# MCU.net
KiCad netlist of a schematic drawn in Altium Designer
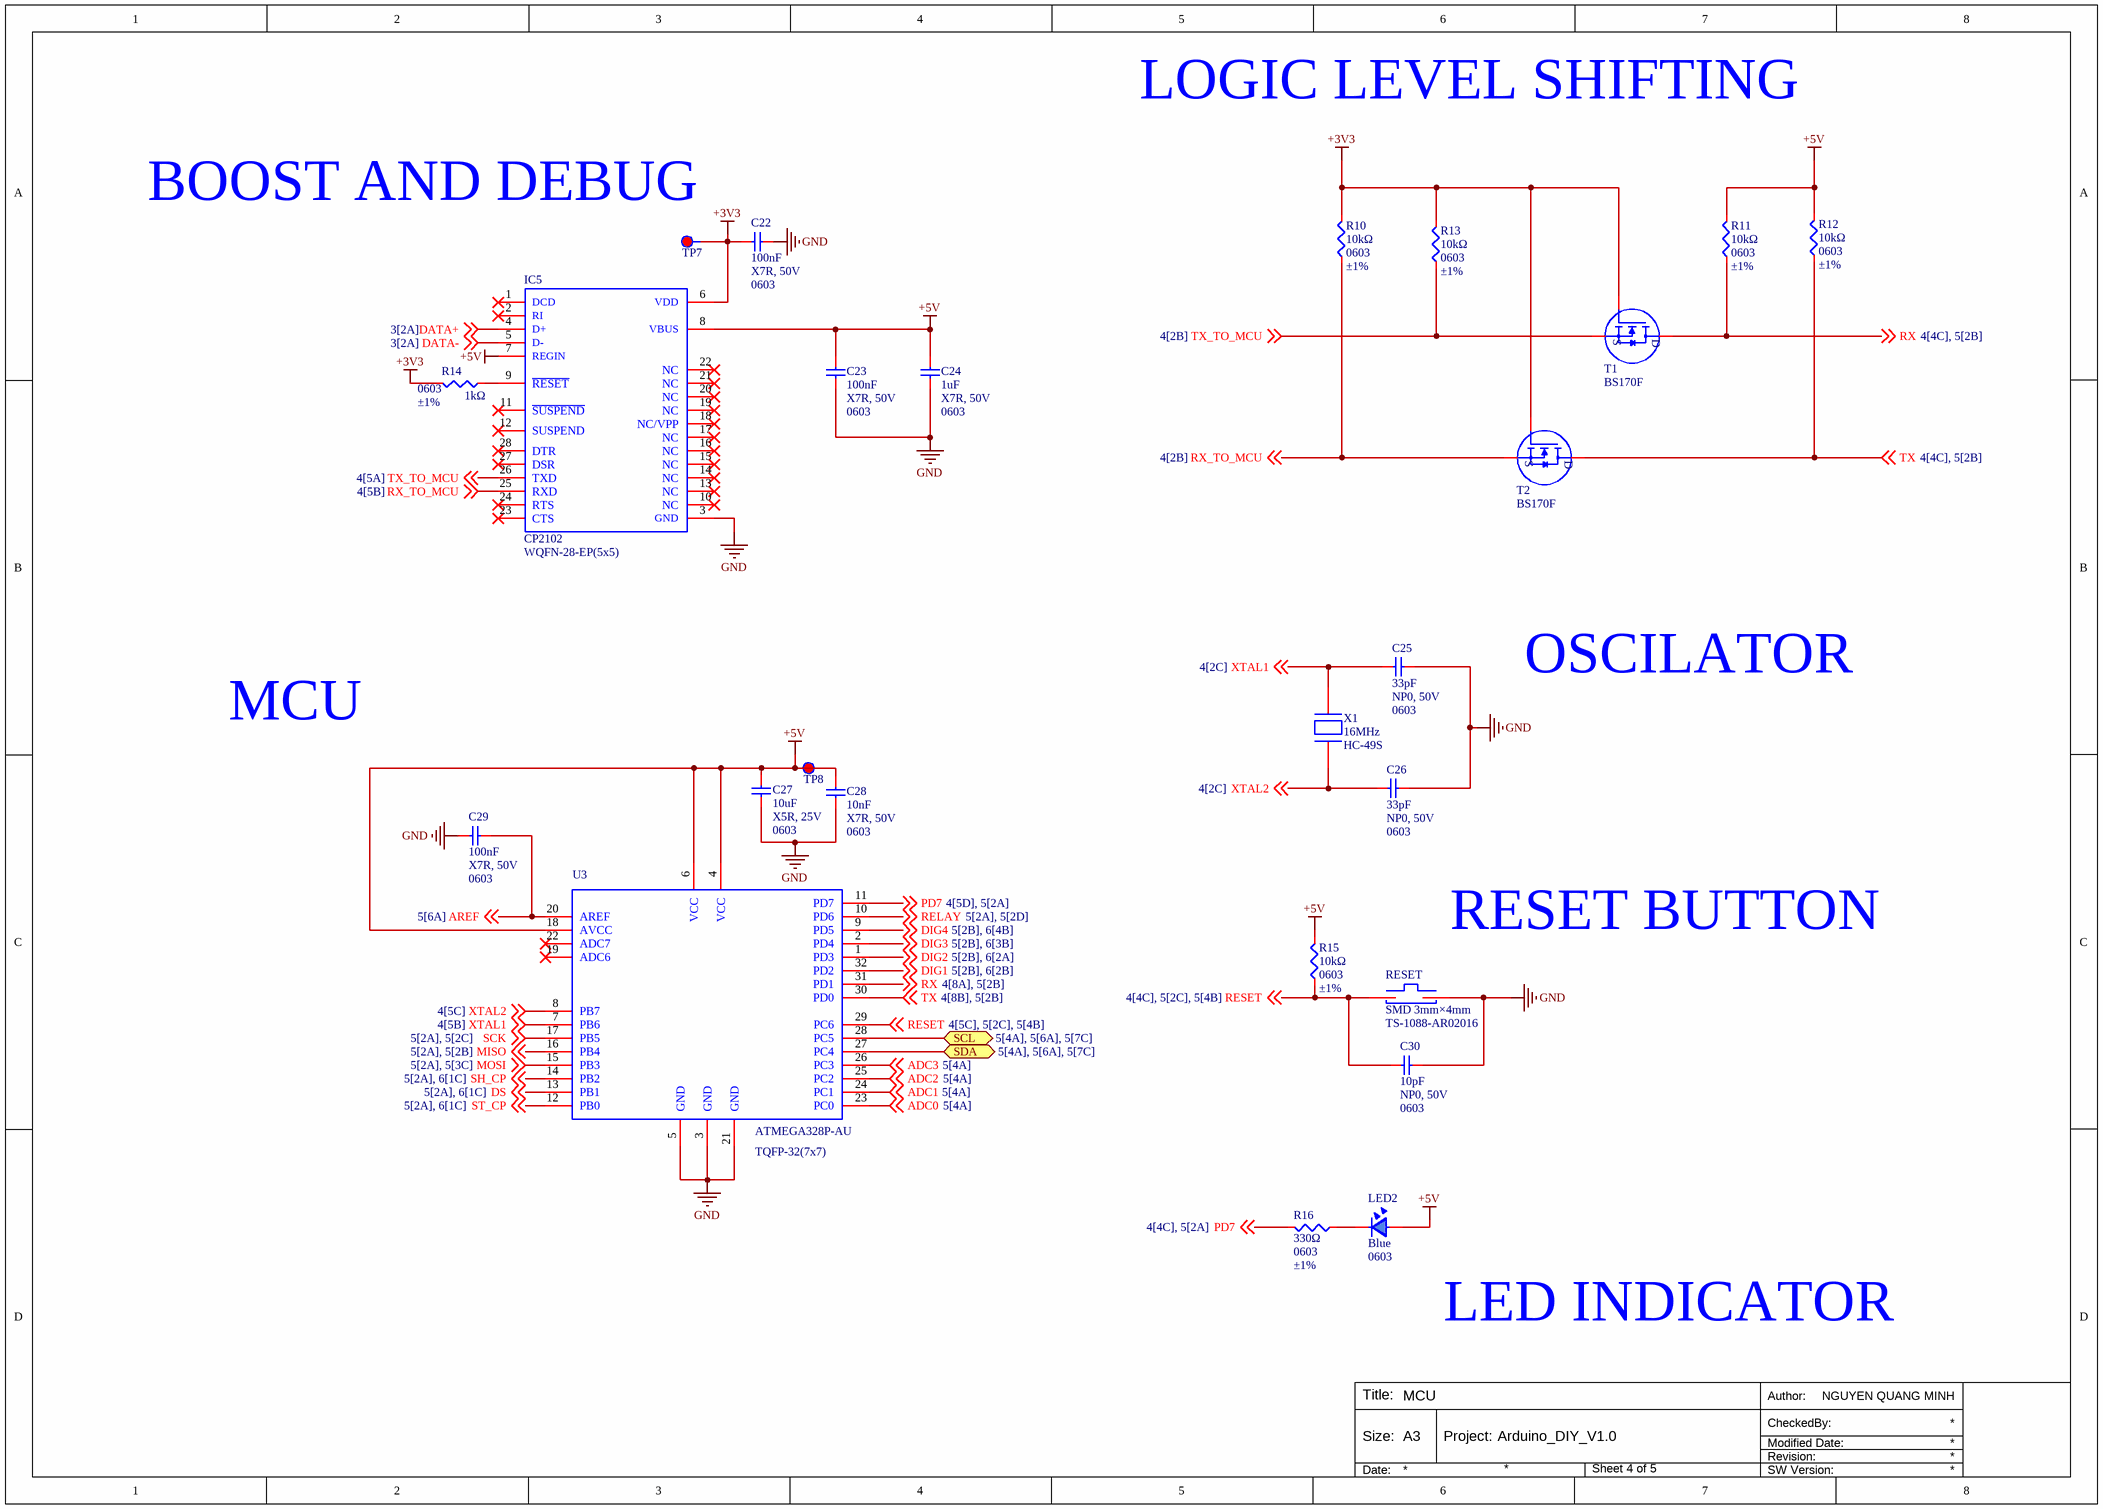
[diagram p0: MCU.SchDoc]

(export (version "E")
  (design (tool "Eeschema 10.0.6"))
  (components
    (comp (ref "C22")
      (value "100nF")
      (footprint "C0603")
      (description "50V 100nF X7R ±10% 0603 Multilayer Ceramic Capacitors MLCC - SMD/SMT ROHS")
      (fields
        (field (name "MANUFACTURER") "YAGEO")
        (field (name "MFR. PART") "CC0603KRX7R9BB104")
        (field (name "TEMPERATURE COEFFICIENT") "X7R, 50V")
        (field (name "PACKAGE") "0603")
      )
      (libsource (lib "Capacitor") (part "C0603_MLCC_100nF_X7R_50V"))
    )
    (comp (ref "C23")
      (value "100nF")
      (footprint "C0603")
      (description "50V 100nF X7R ±10% 0603 Multilayer Ceramic Capacitors MLCC - SMD/SMT ROHS")
      (fields
        (field (name "MANUFACTURER") "YAGEO")
        (field (name "MFR. PART") "CC0603KRX7R9BB104")
        (field (name "TEMPERATURE COEFFICIENT") "X7R, 50V")
        (field (name "PACKAGE") "0603")
      )
      (libsource (lib "Capacitor") (part "C0603_MLCC_100nF_X7R_50V"))
    )
    (comp (ref "C24")
      (value "1uF")
      (footprint "C0603")
      (description "50V 1uF X7R ±10% 0603 Multilayer Ceramic Capacitors MLCC - SMD/SMT ROHS")
      (fields
        (field (name "MANUFACTURER") "YAGEO")
        (field (name "MFR. PART") "CC0603KRX7R9BB105")
        (field (name "TEMPERATURE COEFFICIENT") "X7R, 50V")
        (field (name "PACKAGE") "0603")
      )
      (libsource (lib "Capacitor") (part "C0603_MLCC_1uF_X7R_50V"))
    )
    (comp (ref "C25")
      (value "33pF")
      (footprint "C0603")
      (description "50V 33pF NP0 ±5% 0603 Multilayer Ceramic Capacitors MLCC - SMD/SMT ROHS")
      (fields
        (field (name "MANUFACTURER") "YAGEO")
        (field (name "MFR. PART") "CC0603JRNPO9BN330")
        (field (name "TEMPERATURE COEFFICIENT") "NP0, 50V")
        (field (name "PACKAGE") "0603")
      )
      (libsource (lib "Capacitor") (part "C0603_MLCC_33pF_NP0_50V"))
    )
    (comp (ref "C26")
      (value "33pF")
      (footprint "C0603")
      (description "50V 33pF NP0 ±5% 0603 Multilayer Ceramic Capacitors MLCC - SMD/SMT ROHS")
      (fields
        (field (name "MANUFACTURER") "YAGEO")
        (field (name "MFR. PART") "CC0603JRNPO9BN330")
        (field (name "TEMPERATURE COEFFICIENT") "NP0, 50V")
        (field (name "PACKAGE") "0603")
      )
      (libsource (lib "Capacitor") (part "C0603_MLCC_33pF_NP0_50V"))
    )
    (comp (ref "C27")
      (value "10uF")
      (footprint "C0603")
      (description "25V 10uF X5R ±20% 0603 Multilayer Ceramic Capacitors MLCC - SMD/SMT ROHS")
      (fields
        (field (name "MANUFACTURER") "YAGEO")
        (field (name "MFR. PART") "CC0603MRX5R8BB106")
        (field (name "TEMPERATURE COEFFICIENT") "X5R, 25V")
        (field (name "PACKAGE") "0603")
      )
      (libsource (lib "Capacitor") (part "C0603_MLCC_10uF_X5R_25V"))
    )
    (comp (ref "C28")
      (value "10nF")
      (footprint "C0603")
      (description "50V 10nF X7R ±10% 0603 Multilayer Ceramic Capacitors MLCC - SMD/SMT ROHS")
      (fields
        (field (name "MANUFACTURER") "YAGEO")
        (field (name "MFR. PART") "CC0603KRX7R9BB103")
        (field (name "TEMPERATURE COEFFICIENT") "X7R, 50V")
        (field (name "PACKAGE") "0603")
      )
      (libsource (lib "Capacitor") (part "C0603_MLCC_10nF_X7R_50V"))
    )
    (comp (ref "C29")
      (value "100nF")
      (footprint "C0603")
      (description "50V 100nF X7R ±10% 0603 Multilayer Ceramic Capacitors MLCC - SMD/SMT ROHS")
      (fields
        (field (name "MANUFACTURER") "YAGEO")
        (field (name "MFR. PART") "CC0603KRX7R9BB104")
        (field (name "TEMPERATURE COEFFICIENT") "X7R, 50V")
        (field (name "PACKAGE") "0603")
      )
      (libsource (lib "Capacitor") (part "C0603_MLCC_100nF_X7R_50V"))
    )
    (comp (ref "C30")
      (value "10pF")
      (footprint "C0603")
      (description "50V 10pF NP0 ±5% 0603 Multilayer Ceramic Capacitors MLCC - SMD/SMT ROHS")
      (fields
        (field (name "MANUFACTURER") "YAGEO")
        (field (name "MFR. PART") "CC0603JRNPO9BN100")
        (field (name "TEMPERATURE COEFFICIENT") "NP0, 50V")
        (field (name "PACKAGE") "0603")
      )
      (libsource (lib "Capacitor") (part "C0603_MLCC_10pF_NP0_50V"))
    )
    (comp (ref "IC5")
      (value "CP2102")
      (footprint "WQFN-28-EP(5x5)")
      (description "12Mbps Transceiver WQFN-28-EP(5x5) USB Converters ROHS")
      (fields
        (field (name "MANUFACTURER") "SILICON LABS")
        (field (name "MFR. PART") "CP2102-GMR")
        (field (name "PACKAGE") "WQFN-28-EP(5x5)")
      )
      (libsource (lib "IC") (part "CP2102"))
    )
    (comp (ref "LED2")
      (value "Blue")
      (footprint "LED0603_BLUE")
      (description "2mA 24mcd Water Clear -40℃~+85℃ 470nm Blue 130° 120mW 2.65V 0603 LED Indication - Discrete ROHS")
      (fields
        (field (name "MANUFACTURER") "Kingbright")
        (field (name "MFR. PART") "APT1608LVBC/D")
        (field (name "PACKAGE") "0603")
      )
      (libsource (lib "LED") (part "LED0603_Blue"))
    )
    (comp (ref "R10")
      (value "10kΩ")
      (footprint "R0603")
      (description "100mW Thick Film Resistor 75V ±100ppm/℃ ±1% 10kΩ 0603 Chip Resistor - Surface Mount ROHS")
      (fields
        (field (name "MANUFACTURER") "YAGEO")
        (field (name "MFR. PART") "RC0603FR-0710KL")
        (field (name "PACKAGE") "0603")
        (field (name "TOLERANCE") "±1%")
      )
      (libsource (lib "Resistor") (part "R0603_10kΩ_±1%"))
    )
    (comp (ref "R11")
      (value "10kΩ")
      (footprint "R0603")
      (description "100mW Thick Film Resistor 75V ±100ppm/℃ ±1% 10kΩ 0603 Chip Resistor - Surface Mount ROHS")
      (fields
        (field (name "MANUFACTURER") "YAGEO")
        (field (name "MFR. PART") "RC0603FR-0710KL")
        (field (name "PACKAGE") "0603")
        (field (name "TOLERANCE") "±1%")
      )
      (libsource (lib "Resistor") (part "R0603_10kΩ_±1%"))
    )
    (comp (ref "R12")
      (value "10kΩ")
      (footprint "R0603")
      (description "100mW Thick Film Resistor 75V ±100ppm/℃ ±1% 10kΩ 0603 Chip Resistor - Surface Mount ROHS")
      (fields
        (field (name "MANUFACTURER") "YAGEO")
        (field (name "MFR. PART") "RC0603FR-0710KL")
        (field (name "PACKAGE") "0603")
        (field (name "TOLERANCE") "±1%")
      )
      (libsource (lib "Resistor") (part "R0603_10kΩ_±1%"))
    )
    (comp (ref "R13")
      (value "10kΩ")
      (footprint "R0603")
      (description "100mW Thick Film Resistor 75V ±100ppm/℃ ±1% 10kΩ 0603 Chip Resistor - Surface Mount ROHS")
      (fields
        (field (name "MANUFACTURER") "YAGEO")
        (field (name "MFR. PART") "RC0603FR-0710KL")
        (field (name "PACKAGE") "0603")
        (field (name "TOLERANCE") "±1%")
      )
      (libsource (lib "Resistor") (part "R0603_10kΩ_±1%"))
    )
    (comp (ref "R14")
      (value "1kΩ")
      (footprint "R0603")
      (description "100mW Thick Film Resistor 75V ±100ppm/℃ ±1% 1kΩ 0603 Chip Resistor - Surface Mount ROHS")
      (fields
        (field (name "MANUFACTURER") "YAGEO")
        (field (name "MFR. PART") "RC0603FR-071KL")
        (field (name "PACKAGE") "0603")
        (field (name "TOLERANCE") "±1%")
      )
      (libsource (lib "Resistor") (part "R0603_1kΩ_±1%"))
    )
    (comp (ref "R15")
      (value "10kΩ")
      (footprint "R0603")
      (description "100mW Thick Film Resistor 75V ±100ppm/℃ ±1% 10kΩ 0603 Chip Resistor - Surface Mount ROHS")
      (fields
        (field (name "MANUFACTURER") "YAGEO")
        (field (name "MFR. PART") "RC0603FR-0710KL")
        (field (name "PACKAGE") "0603")
        (field (name "TOLERANCE") "±1%")
      )
      (libsource (lib "Resistor") (part "R0603_10kΩ_±1%"))
    )
    (comp (ref "R16")
      (value "330Ω")
      (footprint "R0603")
      (description "100mW Thick Film Resistor 75V ±100ppm/℃ ±1% 330Ω 0603 Chip Resistor - Surface Mount ROHS")
      (fields
        (field (name "MANUFACTURER") "YAGEO")
        (field (name "MFR. PART") "RC0603FR-07330RL")
        (field (name "PACKAGE") "0603")
        (field (name "TOLERANCE") "±1%")
      )
      (libsource (lib "Resistor") (part "R0603_330Ω_±1%"))
    )
    (comp (ref "RESET")
      (value "SMD 3mm×4mm")
      (footprint "ROUND_BUTTON_SMD 3*4mm")
      (fields
        (field (name "MANUFACTURER") "XUNPU")
        (field (name "LCSC PART") "C720477")
        (field (name "MFR. PART") "TS-1088-AR02016")
      )
      (libsource (lib "BUTTON and SWITCH") (part "SW_BUTTON_SMD_3mm×4mm"))
    )
    (comp (ref "T1")
      (value "BS170F")
      (footprint "SOT-23")
      (description "90V 150uA 5Ω@10V 330mW 3V@1mA 1 N-Channel SOT-23 MOSFETs ROHS")
      (fields (field (name "MANUFACTURER") "DIODES") (field (name "LCSC PART") "C151050"))
      (libsource (lib "BJT and FET") (part "BS170F"))
    )
    (comp (ref "T2")
      (value "BS170F")
      (footprint "SOT-23")
      (description "90V 150uA 5Ω@10V 330mW 3V@1mA 1 N-Channel SOT-23 MOSFETs ROHS")
      (fields (field (name "MANUFACTURER") "DIODES") (field (name "LCSC PART") "C151050"))
      (libsource (lib "BJT and FET") (part "BS170F"))
    )
    (comp (ref "TP7")
      (value "Test Point")
      (footprint "TEST_POINT")
      (libsource (lib "TEST_POINT") (part "TEST_POINT"))
    )
    (comp (ref "TP8")
      (value "Test Point")
      (footprint "TEST_POINT")
      (libsource (lib "TEST_POINT") (part "TEST_POINT"))
    )
    (comp (ref "U3")
      (value "ATMEGA328P-AU")
      (footprint "TQFP-32 (7x7)")
      (description "AVR 20MHz TQFP-32(7x7) Microcontrollers (MCU/MPU/SOC) ROHS")
      (fields
        (field (name "MANUFACTURER") "MICROCHIP")
        (field (name "LCSC PART") "C14877")
        (field (name "PACKAGE") "TQFP-32(7x7)")
      )
      (libsource (lib "MCU") (part "ATMEGA328P-AU"))
    )
    (comp (ref "X1")
      (value "16MHz")
      (footprint "HC-49S")
      (description "16MHz Through Hole Crystal Oscillator 20pF ±20ppm ±30ppm HC-49S Crystals ROHS")
      (fields
        (field (name "MANUFACTURER") "YXC Crystal Oscillators")
        (field (name "MFR. PART") "X49SD16MSD2SC")
        (field (name "PACKAGE") "HC-49S")
      )
      (libsource (lib "CRYSTAL") (part "Crystal_16Mhz_HC49S"))
    )
  )
  (nets
    (net (code "1") (name "+3V3") (class "Default")
      (node (ref "C22") (pin "2") (pinfunction "2_2") (pintype "passive"))
      (node (ref "IC5") (pin "6") (pinfunction "VDD_6") (pintype "passive"))
      (node (ref "R10") (pin "2") (pinfunction "2_2") (pintype "passive"))
      (node (ref "R13") (pin "2") (pinfunction "2_2") (pintype "passive"))
      (node (ref "R14") (pin "2") (pinfunction "2_2") (pintype "passive"))
      (node (ref "T1") (pin "1") (pinfunction "G_1") (pintype "passive"))
      (node (ref "T2") (pin "1") (pinfunction "G_1") (pintype "passive"))
      (node (ref "TP7") (pin "1") (pinfunction "1_1") (pintype "passive"))
    )
    (net (code "2") (name "+5V") (class "Default")
      (node (ref "C23") (pin "2") (pinfunction "2_2") (pintype "passive"))
      (node (ref "C24") (pin "2") (pinfunction "2_2") (pintype "passive"))
      (node (ref "C27") (pin "2") (pinfunction "2_2") (pintype "passive"))
      (node (ref "C28") (pin "2") (pinfunction "2_2") (pintype "passive"))
      (node (ref "IC5") (pin "7") (pinfunction "REGIN_7") (pintype "passive"))
      (node (ref "IC5") (pin "8") (pinfunction "VBUS_8") (pintype "passive"))
      (node (ref "LED2") (pin "1") (pinfunction "1_1") (pintype "passive"))
      (node (ref "R11") (pin "2") (pinfunction "2_2") (pintype "passive"))
      (node (ref "R12") (pin "2") (pinfunction "2_2") (pintype "passive"))
      (node (ref "R15") (pin "2") (pinfunction "2_2") (pintype "passive"))
      (node (ref "TP8") (pin "1") (pinfunction "1_1") (pintype "passive"))
      (node (ref "U3") (pin "18") (pinfunction "AVCC_18") (pintype "passive"))
      (node (ref "U3") (pin "4") (pinfunction "VCC_4") (pintype "passive"))
      (node (ref "U3") (pin "6") (pinfunction "VCC_6") (pintype "passive"))
    )
    (net (code "3") (name "/SCL") (class "Default")
      (node (ref "U3") (pin "28") (pinfunction "PC5_28") (pintype "passive"))
    )
    (net (code "4") (name "/SDA") (class "Default")
      (node (ref "U3") (pin "27") (pinfunction "PC4_27") (pintype "passive"))
    )
    (net (code "5") (name "ADC0") (class "Default")
      (node (ref "U3") (pin "23") (pinfunction "PC0_23") (pintype "passive"))
    )
    (net (code "6") (name "ADC1") (class "Default")
      (node (ref "U3") (pin "24") (pinfunction "PC1_24") (pintype "passive"))
    )
    (net (code "7") (name "ADC2") (class "Default")
      (node (ref "U3") (pin "25") (pinfunction "PC2_25") (pintype "passive"))
    )
    (net (code "8") (name "ADC3") (class "Default")
      (node (ref "U3") (pin "26") (pinfunction "PC3_26") (pintype "passive"))
    )
    (net (code "9") (name "AREF") (class "Default")
      (node (ref "C29") (pin "2") (pinfunction "2_2") (pintype "passive"))
      (node (ref "U3") (pin "20") (pinfunction "AREF_20") (pintype "passive"))
    )
    (net (code "10") (name "DATA+") (class "Default")
      (node (ref "IC5") (pin "4") (pinfunction "D+_4") (pintype "passive"))
    )
    (net (code "11") (name "DATA-") (class "Default")
      (node (ref "IC5") (pin "5") (pinfunction "D-_5") (pintype "passive"))
    )
    (net (code "12") (name "DIG1") (class "Default")
      (node (ref "U3") (pin "32") (pinfunction "PD2_32") (pintype "passive"))
    )
    (net (code "13") (name "DIG2") (class "Default")
      (node (ref "U3") (pin "1") (pinfunction "PD3_1") (pintype "passive"))
    )
    (net (code "14") (name "DIG3") (class "Default")
      (node (ref "U3") (pin "2") (pinfunction "PD4_2") (pintype "passive"))
    )
    (net (code "15") (name "DIG4") (class "Default")
      (node (ref "U3") (pin "9") (pinfunction "PD5_9") (pintype "passive"))
    )
    (net (code "16") (name "DS") (class "Default")
      (node (ref "U3") (pin "13") (pinfunction "PB1_13") (pintype "passive"))
    )
    (net (code "17") (name "GND") (class "Default")
      (node (ref "C22") (pin "1") (pinfunction "1_1") (pintype "passive"))
      (node (ref "C23") (pin "1") (pinfunction "1_1") (pintype "passive"))
      (node (ref "C24") (pin "1") (pinfunction "1_1") (pintype "passive"))
      (node (ref "C25") (pin "2") (pinfunction "2_2") (pintype "passive"))
      (node (ref "C26") (pin "2") (pinfunction "2_2") (pintype "passive"))
      (node (ref "C27") (pin "1") (pinfunction "1_1") (pintype "passive"))
      (node (ref "C28") (pin "1") (pinfunction "1_1") (pintype "passive"))
      (node (ref "C29") (pin "1") (pinfunction "1_1") (pintype "passive"))
      (node (ref "C30") (pin "2") (pinfunction "2_2") (pintype "passive"))
      (node (ref "IC5") (pin "3") (pinfunction "GND_3") (pintype "passive"))
      (node (ref "RESET") (pin "2") (pinfunction "2_2") (pintype "passive"))
      (node (ref "U3") (pin "21") (pinfunction "GND_21") (pintype "passive"))
      (node (ref "U3") (pin "3") (pinfunction "GND_3") (pintype "passive"))
      (node (ref "U3") (pin "5") (pinfunction "GND_5") (pintype "passive"))
    )
    (net (code "18") (name "MISO") (class "Default")
      (node (ref "U3") (pin "16") (pinfunction "PB4_16") (pintype "passive"))
    )
    (net (code "19") (name "MOSI") (class "Default")
      (node (ref "U3") (pin "15") (pinfunction "PB3_15") (pintype "passive"))
    )
    (net (code "20") (name "Net-(IC5-~{RESET})") (class "Default")
      (node (ref "IC5") (pin "9") (pinfunction "~{RESET}_9") (pintype "passive"))
      (node (ref "R14") (pin "1") (pinfunction "1_1") (pintype "passive"))
    )
    (net (code "21") (name "Net-(LED2-Pad2)") (class "Default")
      (node (ref "LED2") (pin "2") (pinfunction "2_2") (pintype "passive"))
      (node (ref "R16") (pin "2") (pinfunction "2_2") (pintype "passive"))
    )
    (net (code "22") (name "PD7") (class "Default")
      (node (ref "R16") (pin "1") (pinfunction "1_1") (pintype "passive"))
      (node (ref "U3") (pin "11") (pinfunction "PD7_11") (pintype "passive"))
    )
    (net (code "23") (name "RELAY") (class "Default")
      (node (ref "U3") (pin "10") (pinfunction "PD6_10") (pintype "passive"))
    )
    (net (code "24") (name "RESET") (class "Default")
      (node (ref "C30") (pin "1") (pinfunction "1_1") (pintype "passive"))
      (node (ref "R15") (pin "1") (pinfunction "1_1") (pintype "passive"))
      (node (ref "RESET") (pin "1") (pinfunction "1_1") (pintype "passive"))
      (node (ref "U3") (pin "29") (pinfunction "PC6_29") (pintype "passive"))
    )
    (net (code "25") (name "RX") (class "Default")
      (node (ref "R11") (pin "1") (pinfunction "1_1") (pintype "passive"))
      (node (ref "T1") (pin "3") (pinfunction "D_3") (pintype "passive"))
      (node (ref "U3") (pin "31") (pinfunction "PD1_31") (pintype "passive"))
    )
    (net (code "26") (name "RX_TO_MCU") (class "Default")
      (node (ref "IC5") (pin "25") (pinfunction "RXD_25") (pintype "passive"))
      (node (ref "R10") (pin "1") (pinfunction "1_1") (pintype "passive"))
      (node (ref "T2") (pin "2") (pinfunction "S_2") (pintype "passive"))
    )
    (net (code "27") (name "SCK") (class "Default")
      (node (ref "U3") (pin "17") (pinfunction "PB5_17") (pintype "passive"))
    )
    (net (code "28") (name "SH_CP") (class "Default")
      (node (ref "U3") (pin "14") (pinfunction "PB2_14") (pintype "passive"))
    )
    (net (code "29") (name "ST_CP") (class "Default")
      (node (ref "U3") (pin "12") (pinfunction "PB0_12") (pintype "passive"))
    )
    (net (code "30") (name "TX") (class "Default")
      (node (ref "R12") (pin "1") (pinfunction "1_1") (pintype "passive"))
      (node (ref "T2") (pin "3") (pinfunction "D_3") (pintype "passive"))
      (node (ref "U3") (pin "30") (pinfunction "PD0_30") (pintype "passive"))
    )
    (net (code "31") (name "TX_TO_MCU") (class "Default")
      (node (ref "IC5") (pin "26") (pinfunction "TXD_26") (pintype "passive"))
      (node (ref "R13") (pin "1") (pinfunction "1_1") (pintype "passive"))
      (node (ref "T1") (pin "2") (pinfunction "S_2") (pintype "passive"))
    )
    (net (code "32") (name "XTAL1") (class "Default")
      (node (ref "C25") (pin "1") (pinfunction "1_1") (pintype "passive"))
      (node (ref "U3") (pin "7") (pinfunction "PB6_7") (pintype "passive"))
      (node (ref "X1") (pin "2") (pinfunction "2_2") (pintype "passive"))
    )
    (net (code "33") (name "XTAL2") (class "Default")
      (node (ref "C26") (pin "1") (pinfunction "1_1") (pintype "passive"))
      (node (ref "U3") (pin "8") (pinfunction "PB7_8") (pintype "passive"))
      (node (ref "X1") (pin "1") (pinfunction "1_1") (pintype "passive"))
    )
    (net (code "34") (name "unconnected-(IC5-CTS-Pad23)") (class "Default")
      (node (ref "IC5") (pin "23") (pinfunction "CTS_23") (pintype "passive+no_connect"))
    )
    (net (code "35") (name "unconnected-(IC5-DCD-Pad1)") (class "Default")
      (node (ref "IC5") (pin "1") (pinfunction "DCD_1") (pintype "passive+no_connect"))
    )
    (net (code "36") (name "unconnected-(IC5-DSR-Pad27)") (class "Default")
      (node (ref "IC5") (pin "27") (pinfunction "DSR_27") (pintype "passive+no_connect"))
    )
    (net (code "37") (name "unconnected-(IC5-DTR-Pad28)") (class "Default")
      (node (ref "IC5") (pin "28") (pinfunction "DTR_28") (pintype "passive+no_connect"))
    )
    (net (code "38") (name "unconnected-(IC5-NC-Pad10)") (class "Default")
      (node (ref "IC5") (pin "10") (pinfunction "NC_10") (pintype "passive+no_connect"))
    )
    (net (code "39") (name "unconnected-(IC5-NC-Pad13)") (class "Default")
      (node (ref "IC5") (pin "13") (pinfunction "NC_13") (pintype "passive+no_connect"))
    )
    (net (code "40") (name "unconnected-(IC5-NC-Pad14)") (class "Default")
      (node (ref "IC5") (pin "14") (pinfunction "NC_14") (pintype "passive+no_connect"))
    )
    (net (code "41") (name "unconnected-(IC5-NC-Pad15)") (class "Default")
      (node (ref "IC5") (pin "15") (pinfunction "NC_15") (pintype "passive+no_connect"))
    )
    (net (code "42") (name "unconnected-(IC5-NC-Pad16)") (class "Default")
      (node (ref "IC5") (pin "16") (pinfunction "NC_16") (pintype "passive+no_connect"))
    )
    (net (code "43") (name "unconnected-(IC5-NC-Pad17)") (class "Default")
      (node (ref "IC5") (pin "17") (pinfunction "NC_17") (pintype "passive+no_connect"))
    )
    (net (code "44") (name "unconnected-(IC5-NC-Pad19)") (class "Default")
      (node (ref "IC5") (pin "19") (pinfunction "NC_19") (pintype "passive+no_connect"))
    )
    (net (code "45") (name "unconnected-(IC5-NC-Pad20)") (class "Default")
      (node (ref "IC5") (pin "20") (pinfunction "NC_20") (pintype "passive+no_connect"))
    )
    (net (code "46") (name "unconnected-(IC5-NC-Pad21)") (class "Default")
      (node (ref "IC5") (pin "21") (pinfunction "NC_21") (pintype "passive+no_connect"))
    )
    (net (code "47") (name "unconnected-(IC5-NC-Pad22)") (class "Default")
      (node (ref "IC5") (pin "22") (pinfunction "NC_22") (pintype "passive+no_connect"))
    )
    (net (code "48") (name "unconnected-(IC5-NC{slash}VPP-Pad18)") (class "Default")
      (node (ref "IC5") (pin "18") (pinfunction "NC/VPP_18") (pintype "passive+no_connect"))
    )
    (net (code "49") (name "unconnected-(IC5-RI-Pad2)") (class "Default")
      (node (ref "IC5") (pin "2") (pinfunction "RI_2") (pintype "passive+no_connect"))
    )
    (net (code "50") (name "unconnected-(IC5-RTS-Pad24)") (class "Default")
      (node (ref "IC5") (pin "24") (pinfunction "RTS_24") (pintype "passive+no_connect"))
    )
    (net (code "51") (name "unconnected-(IC5-SUSPEND-Pad12)") (class "Default")
      (node (ref "IC5") (pin "12") (pinfunction "SUSPEND_12") (pintype "passive+no_connect"))
    )
    (net (code "52") (name "unconnected-(IC5-~{SUSPEND}-Pad11)") (class "Default")
      (node (ref "IC5") (pin "11") (pinfunction "~{SUSPEND}_11") (pintype "passive+no_connect"))
    )
    (net (code "53") (name "unconnected-(U3-ADC6-Pad19)") (class "Default")
      (node (ref "U3") (pin "19") (pinfunction "ADC6_19") (pintype "passive+no_connect"))
    )
    (net (code "54") (name "unconnected-(U3-ADC7-Pad22)") (class "Default")
      (node (ref "U3") (pin "22") (pinfunction "ADC7_22") (pintype "passive+no_connect"))
    )
  )
)
